# quad-hybrid-QCN-19.net
KiCad netlist of a schematic drawn in EAGLE
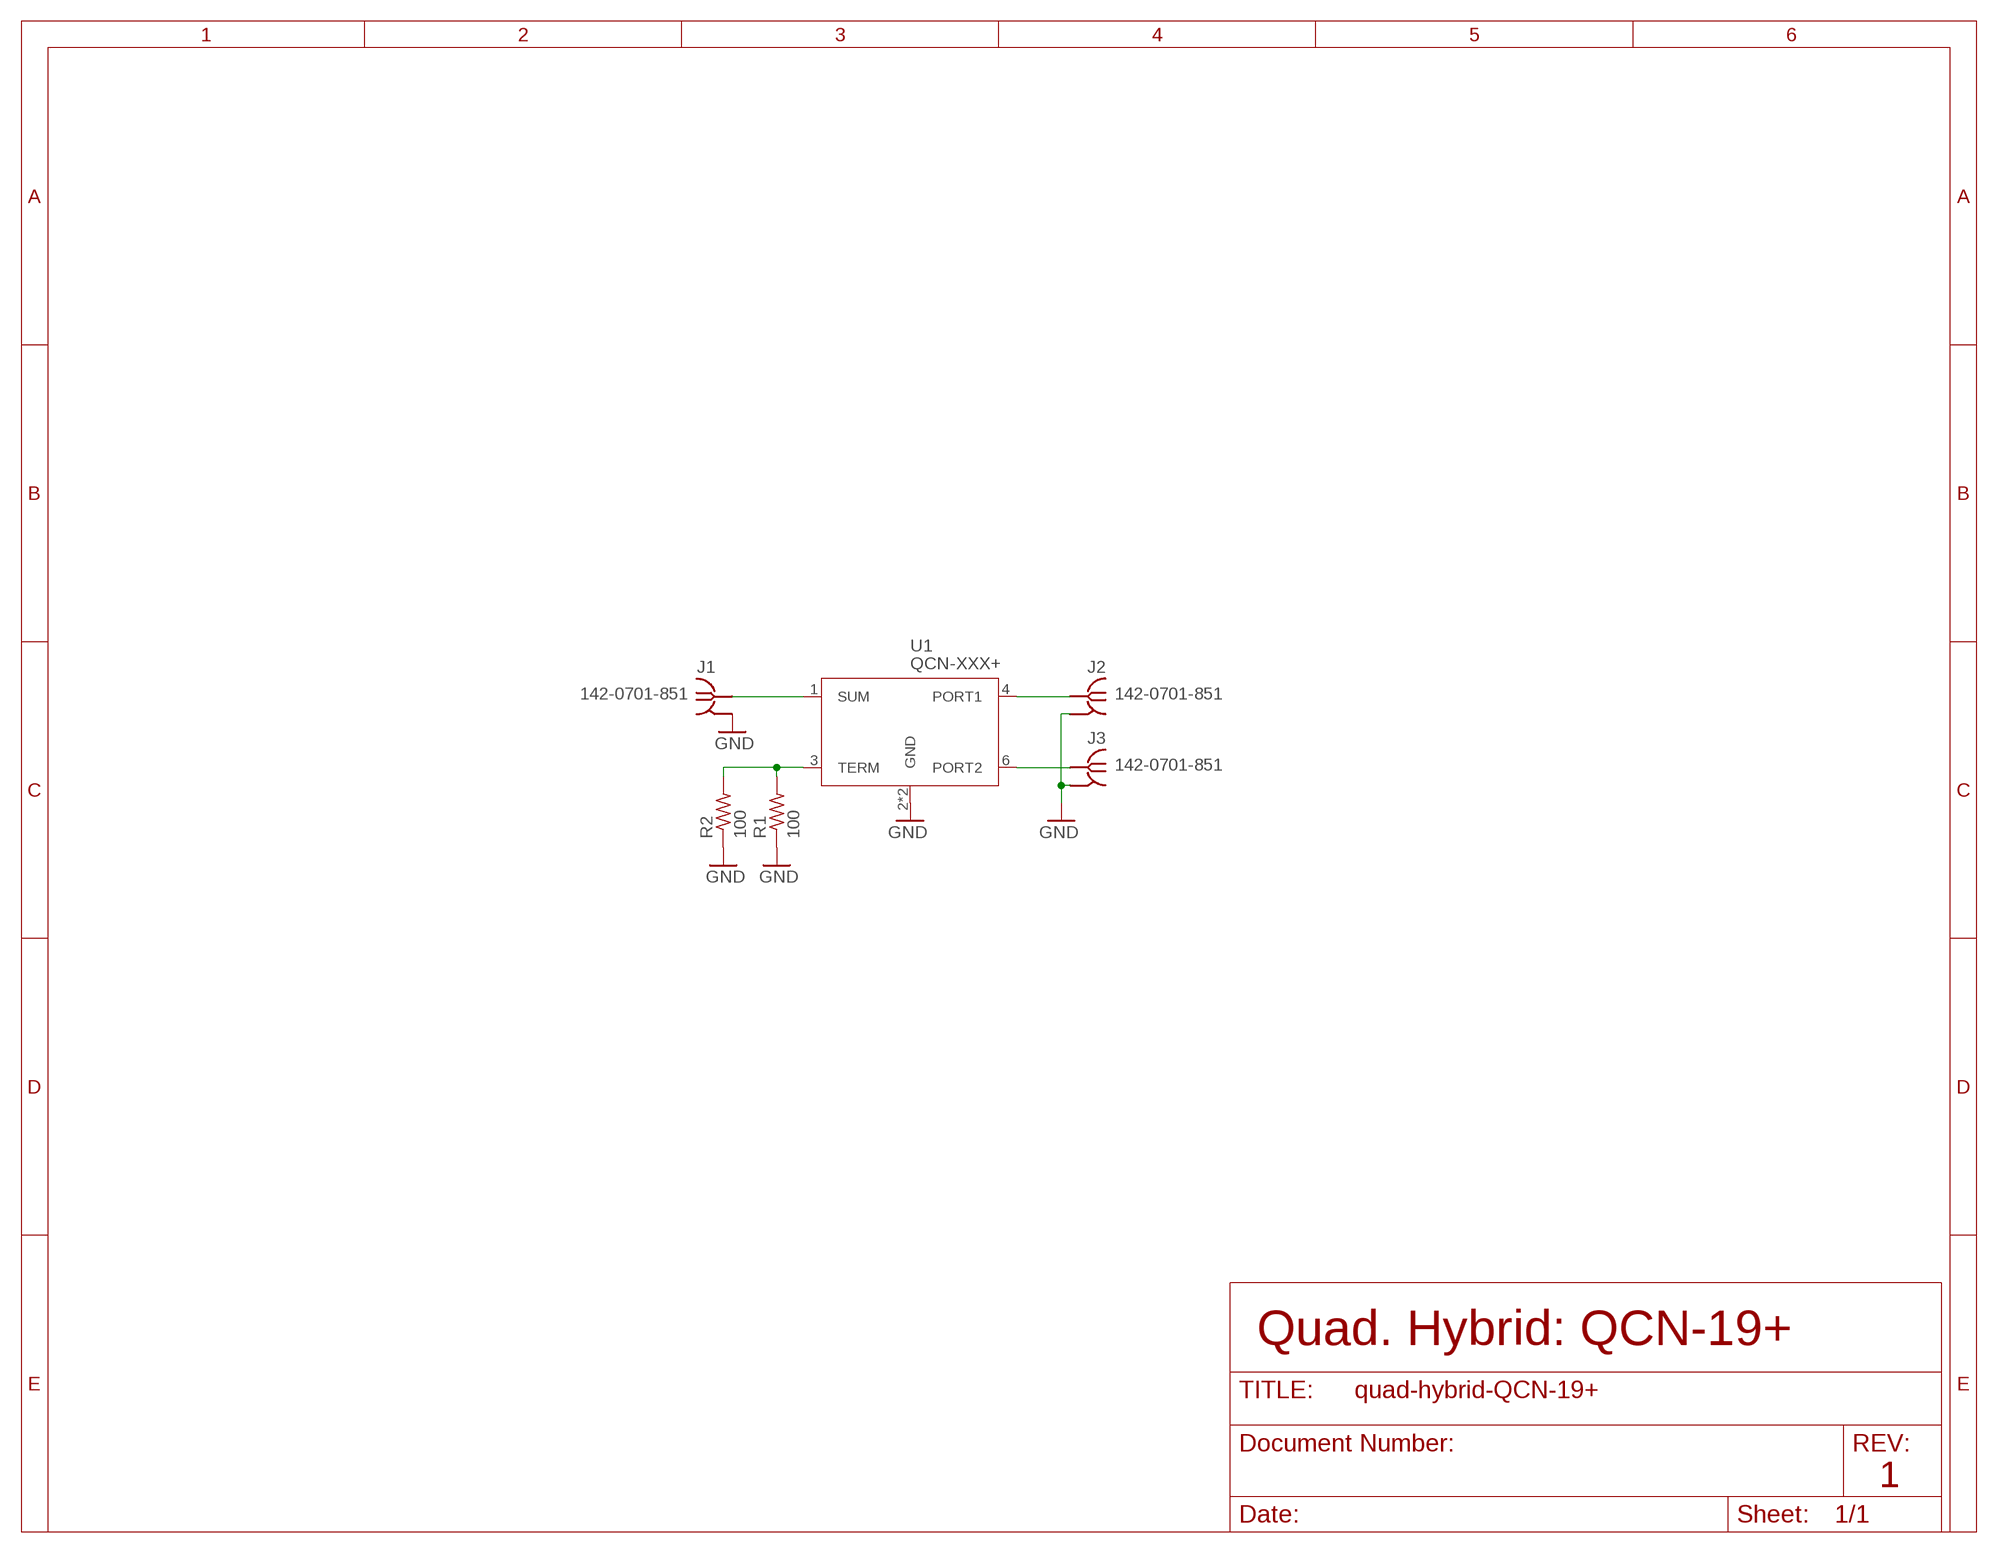
[diagram p0: schematic, sheet 1]

(export (version "E")
  (design (tool "Eeschema 10.0.6"))
  (components
    (comp (ref "J1")
      (value "142-0701-851")
      (footprint "eagle-import:142-0701-851")
      (libsource (lib "eagle-import") (part "142-0701-851"))
    )
    (comp (ref "J2")
      (value "142-0701-851")
      (footprint "eagle-import:142-0701-851")
      (libsource (lib "eagle-import") (part "142-0701-851"))
    )
    (comp (ref "J3")
      (value "142-0701-851")
      (footprint "eagle-import:142-0701-851")
      (libsource (lib "eagle-import") (part "142-0701-851"))
    )
    (comp (ref "R1")
      (value "100")
      (footprint "eagle-import:.0402-C-NOSILK")
      (libsource (lib "eagle-import") (part "R-US_0402-C-NOSILK"))
    )
    (comp (ref "R2")
      (value "100")
      (footprint "eagle-import:.0402-C-NOSILK")
      (libsource (lib "eagle-import") (part "R-US_0402-C-NOSILK"))
    )
    (comp (ref "U1")
      (value "QCN-XXX+")
      (footprint "eagle-import:QCN-XXX+")
      (libsource (lib "eagle-import") (part "QCN-XXX+"))
    )
  )
  (nets
    (net (code "1") (name "GND") (class "Default")
      (node (ref "J1") (pin "GND1") (pinfunction "GND_GND1") (pintype "bidirectional"))
      (node (ref "J1") (pin "GND2") (pinfunction "GND_GND2") (pintype "bidirectional"))
      (node (ref "J1") (pin "GND3") (pinfunction "GND_GND3") (pintype "bidirectional"))
      (node (ref "J1") (pin "GND4") (pinfunction "GND_GND4") (pintype "bidirectional"))
      (node (ref "J2") (pin "GND1") (pinfunction "GND_GND1") (pintype "bidirectional"))
      (node (ref "J2") (pin "GND2") (pinfunction "GND_GND2") (pintype "bidirectional"))
      (node (ref "J2") (pin "GND3") (pinfunction "GND_GND3") (pintype "bidirectional"))
      (node (ref "J2") (pin "GND4") (pinfunction "GND_GND4") (pintype "bidirectional"))
      (node (ref "J3") (pin "GND1") (pinfunction "GND_GND1") (pintype "bidirectional"))
      (node (ref "J3") (pin "GND2") (pinfunction "GND_GND2") (pintype "bidirectional"))
      (node (ref "J3") (pin "GND3") (pinfunction "GND_GND3") (pintype "bidirectional"))
      (node (ref "J3") (pin "GND4") (pinfunction "GND_GND4") (pintype "bidirectional"))
      (node (ref "R1") (pin "1") (pinfunction "1_1") (pintype "passive"))
      (node (ref "R2") (pin "1") (pinfunction "1_1") (pintype "passive"))
      (node (ref "U1") (pin "2") (pinfunction "GND_2") (pintype "power_in"))
      (node (ref "U1") (pin "5") (pinfunction "GND_5") (pintype "power_in"))
    )
    (net (code "2") (name "Net-(J1-RF)") (class "Default")
      (node (ref "J1") (pin "RF1") (pinfunction "RF_RF1") (pintype "bidirectional"))
      (node (ref "U1") (pin "1") (pinfunction "SUM_1") (pintype "bidirectional"))
    )
    (net (code "3") (name "Net-(J2-RF)") (class "Default")
      (node (ref "J2") (pin "RF1") (pinfunction "RF_RF1") (pintype "bidirectional"))
      (node (ref "U1") (pin "4") (pinfunction "PORT1_4") (pintype "bidirectional"))
    )
    (net (code "4") (name "Net-(J3-RF)") (class "Default")
      (node (ref "J3") (pin "RF1") (pinfunction "RF_RF1") (pintype "bidirectional"))
      (node (ref "U1") (pin "6") (pinfunction "PORT2_6") (pintype "bidirectional"))
    )
    (net (code "5") (name "Net-(U1-TERM)") (class "Default")
      (node (ref "R1") (pin "2") (pinfunction "2_2") (pintype "passive"))
      (node (ref "R2") (pin "2") (pinfunction "2_2") (pintype "passive"))
      (node (ref "U1") (pin "3") (pinfunction "TERM_3") (pintype "bidirectional"))
    )
  )
)
